# CCM4201S_MAIN_Board_V1-PIJIAKUN_20260819.net
KiCad netlist of a schematic drawn in Altium Designer
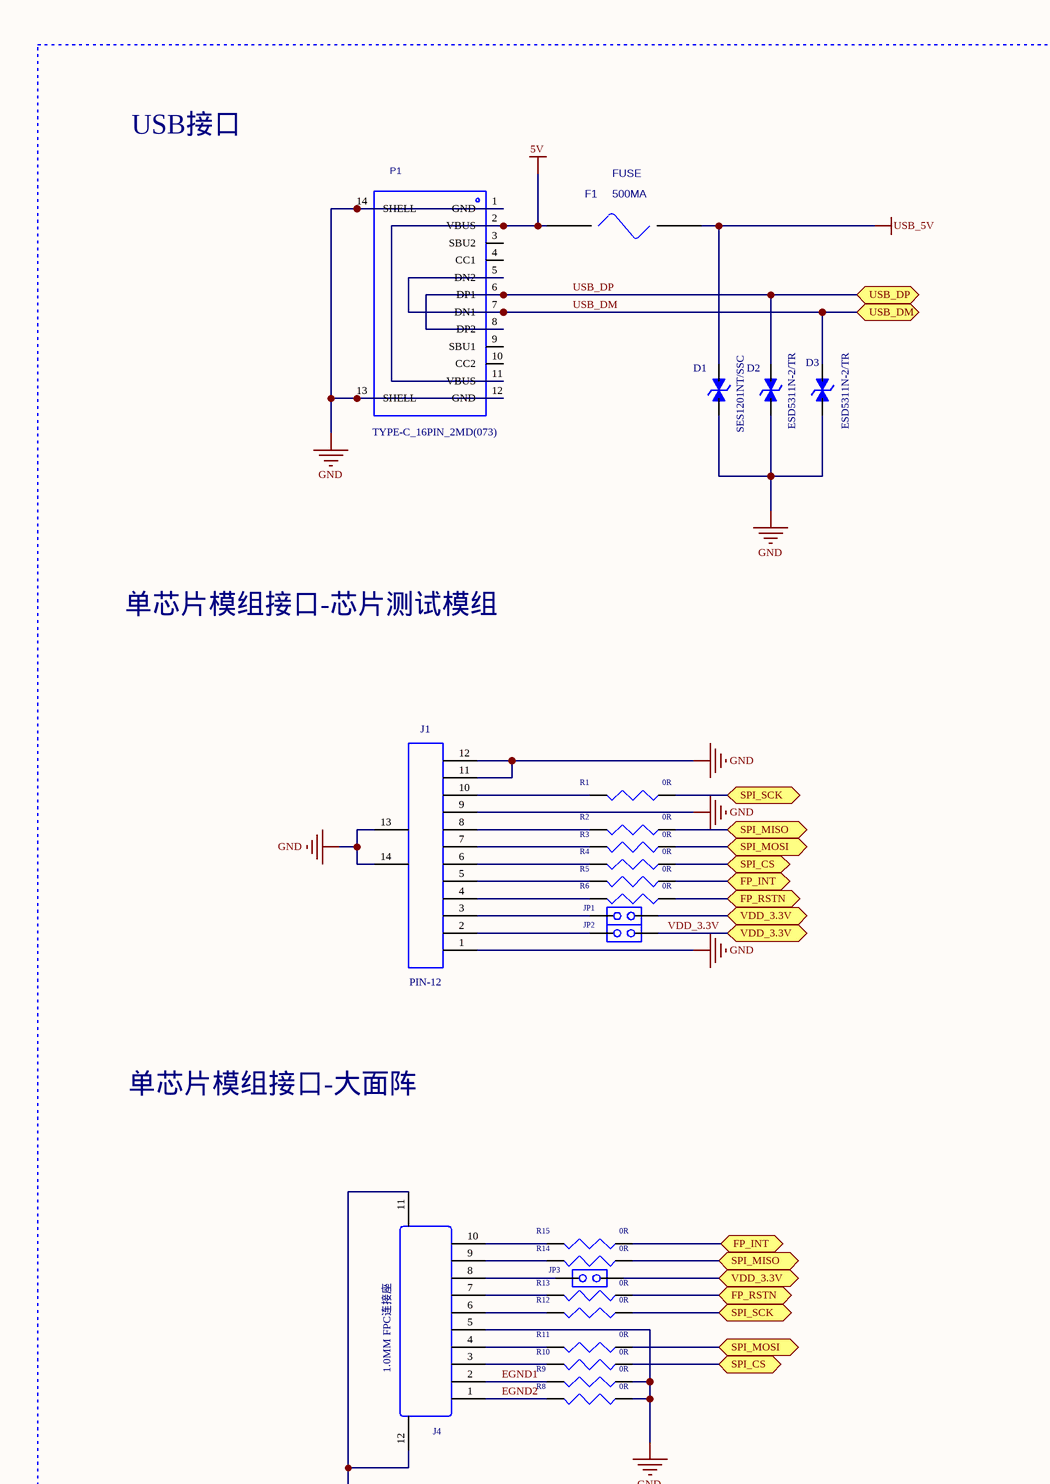
[diagram p0: CCM4201S_MAIN_Board_V1-PIJIAKUN_20260819_SCH.SchDoc, top left]
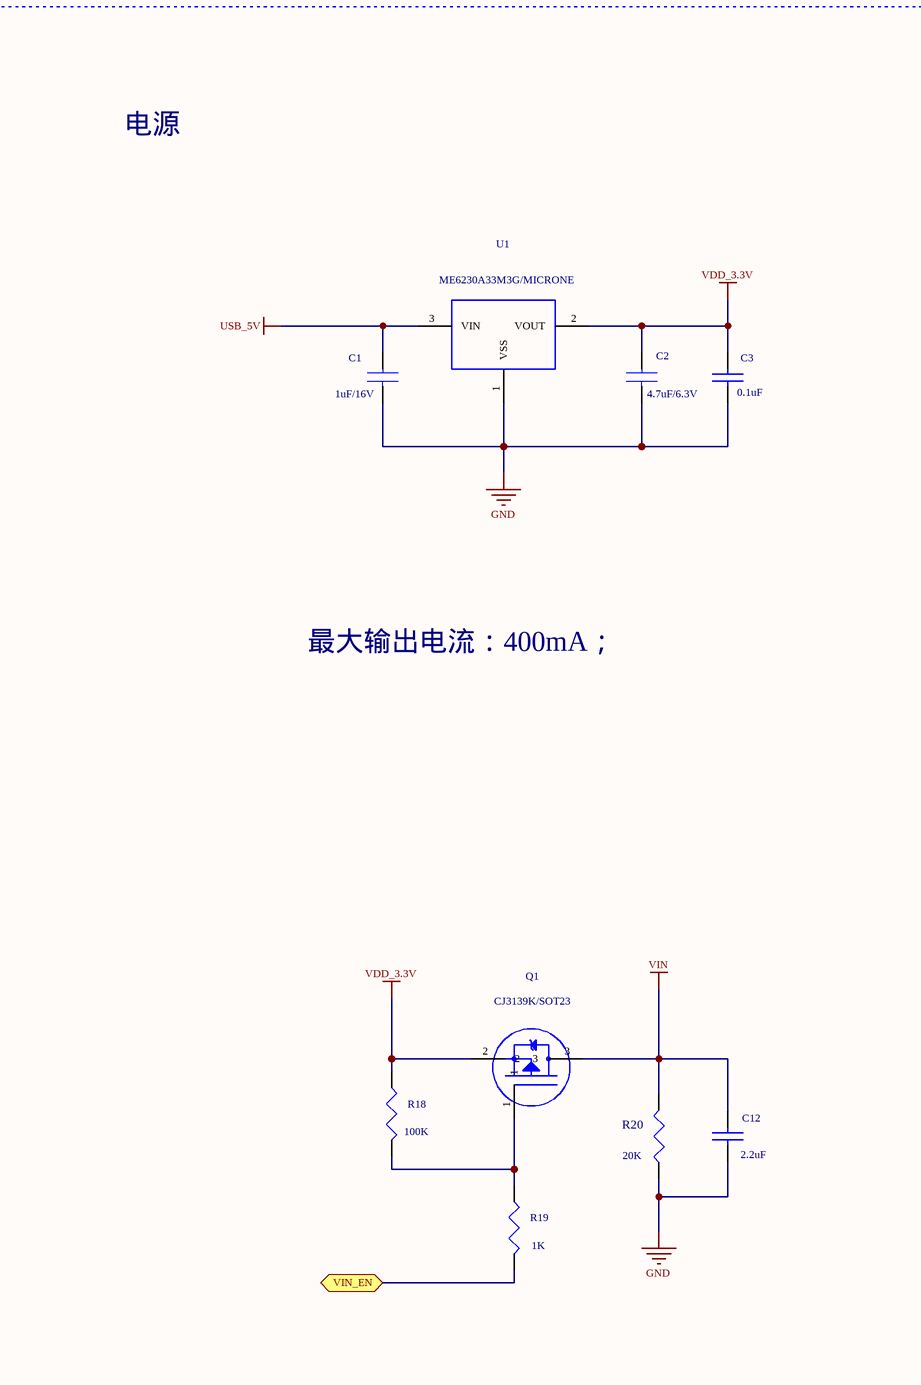
[diagram p1: CCM4201S_MAIN_Board_V1-PIJIAKUN_20260819_SCH.SchDoc, top middle]
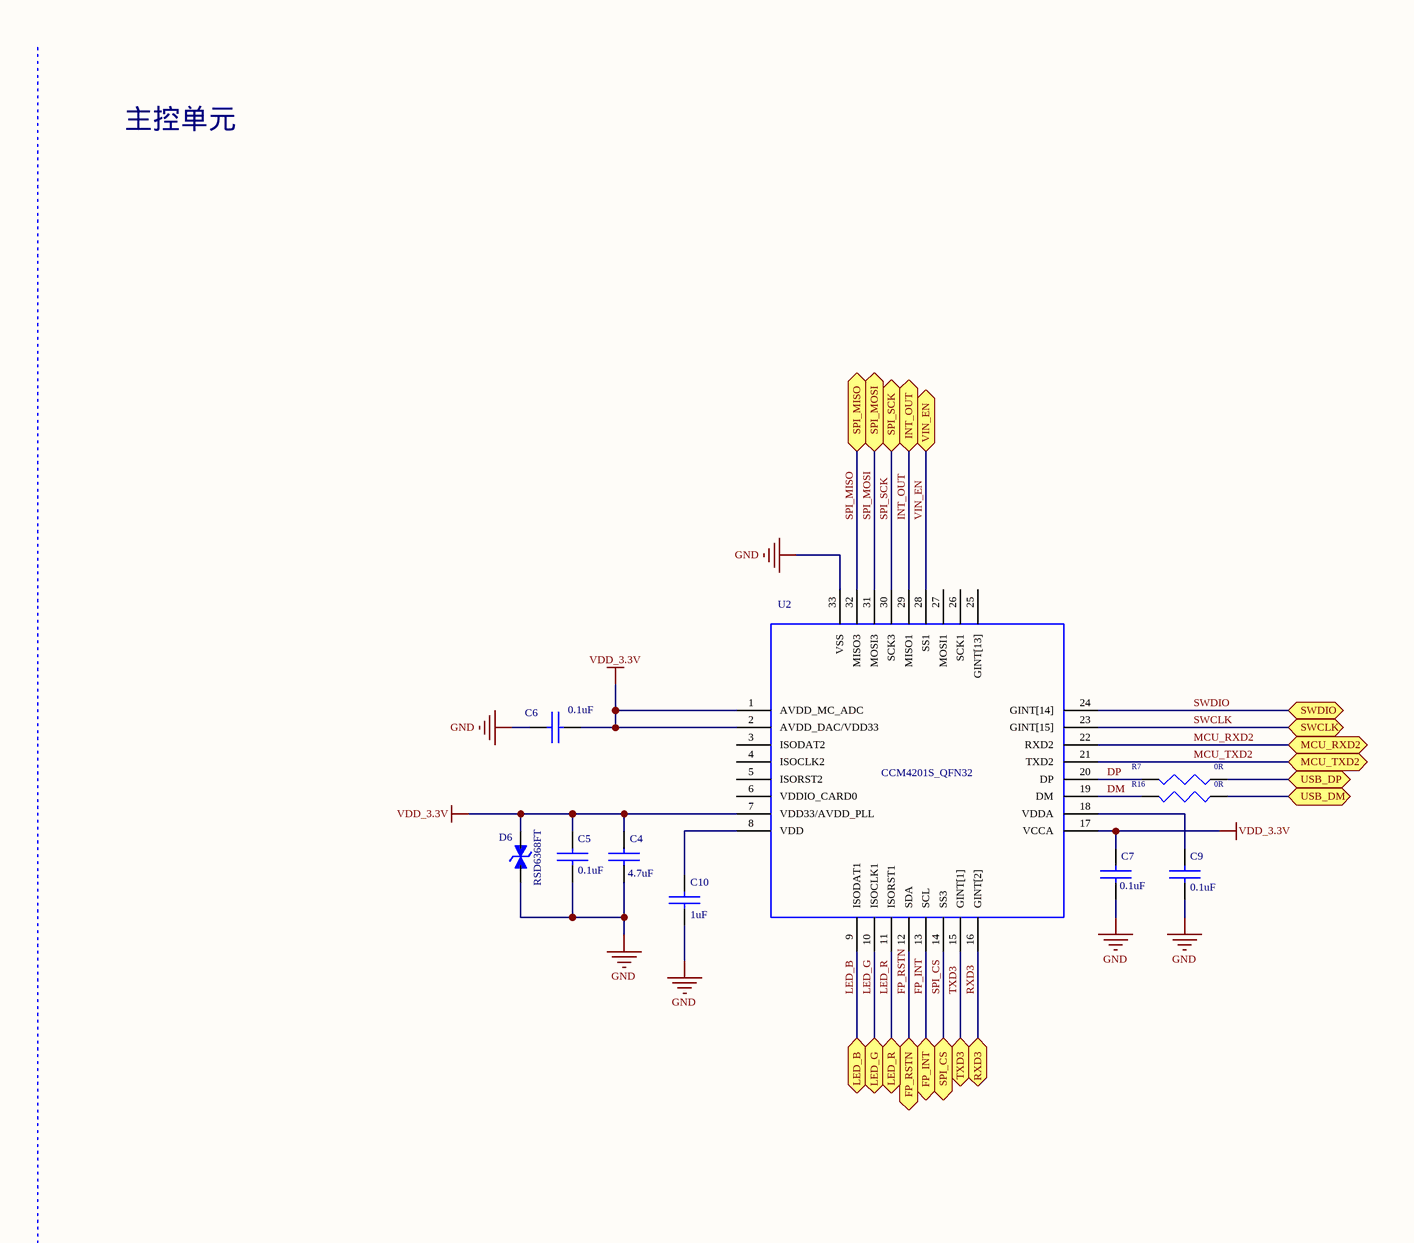
[diagram p2: CCM4201S_MAIN_Board_V1-PIJIAKUN_20260819_SCH.SchDoc, top right]
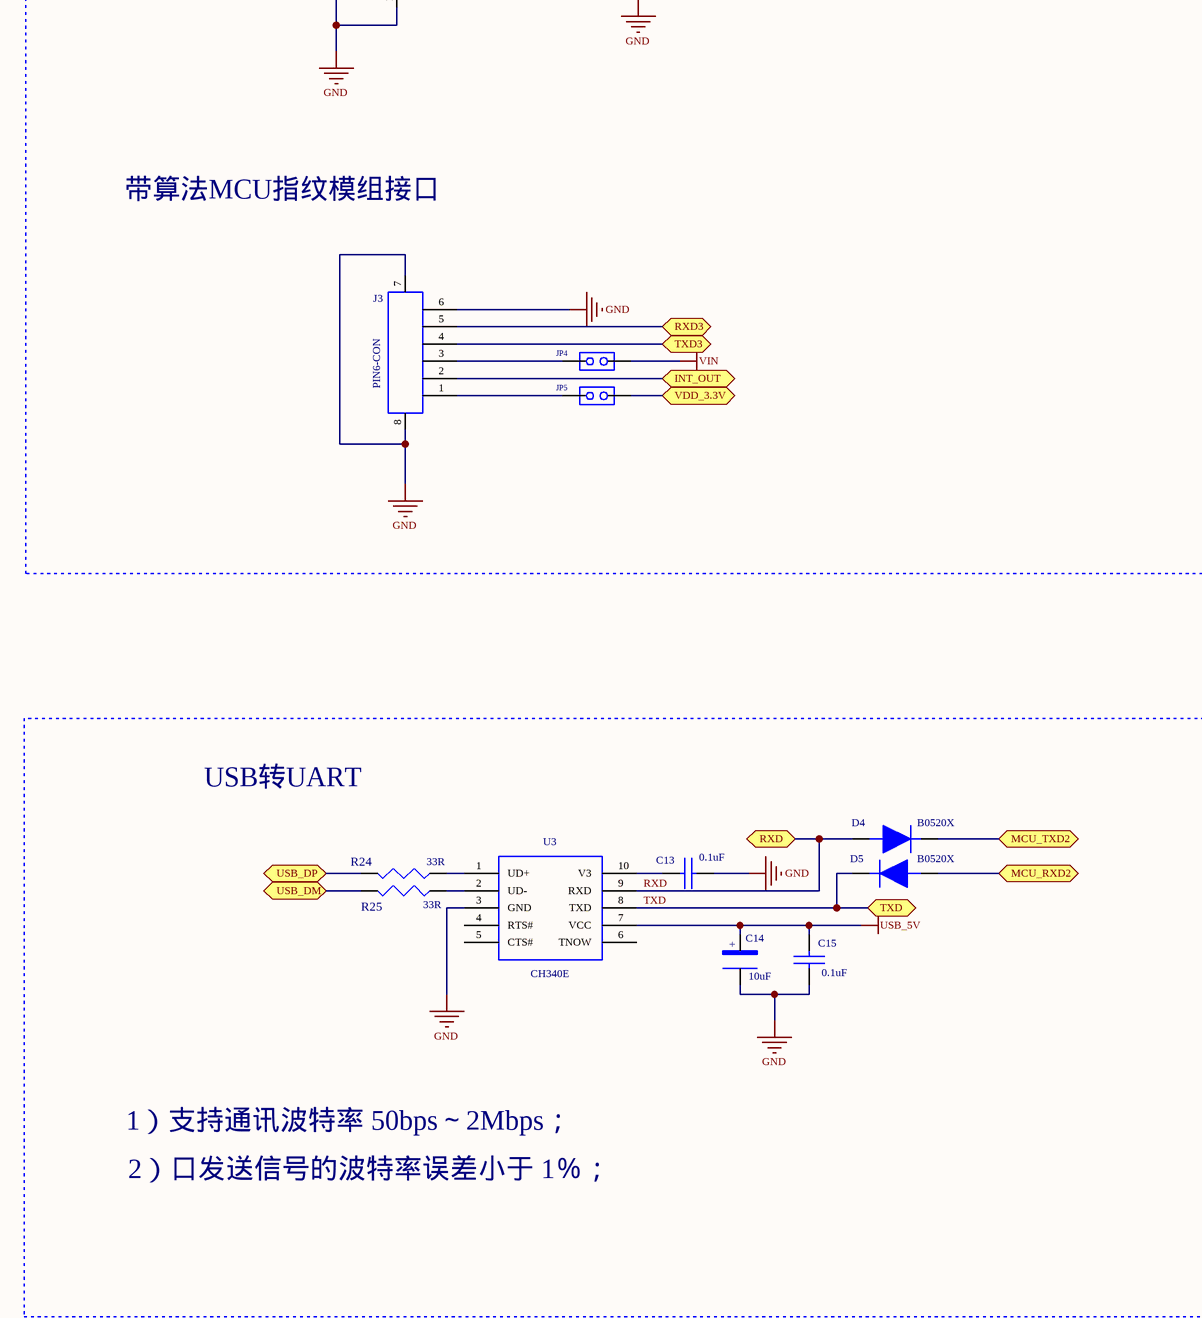
[diagram p3: CCM4201S_MAIN_Board_V1-PIJIAKUN_20260819_SCH.SchDoc, bottom left]
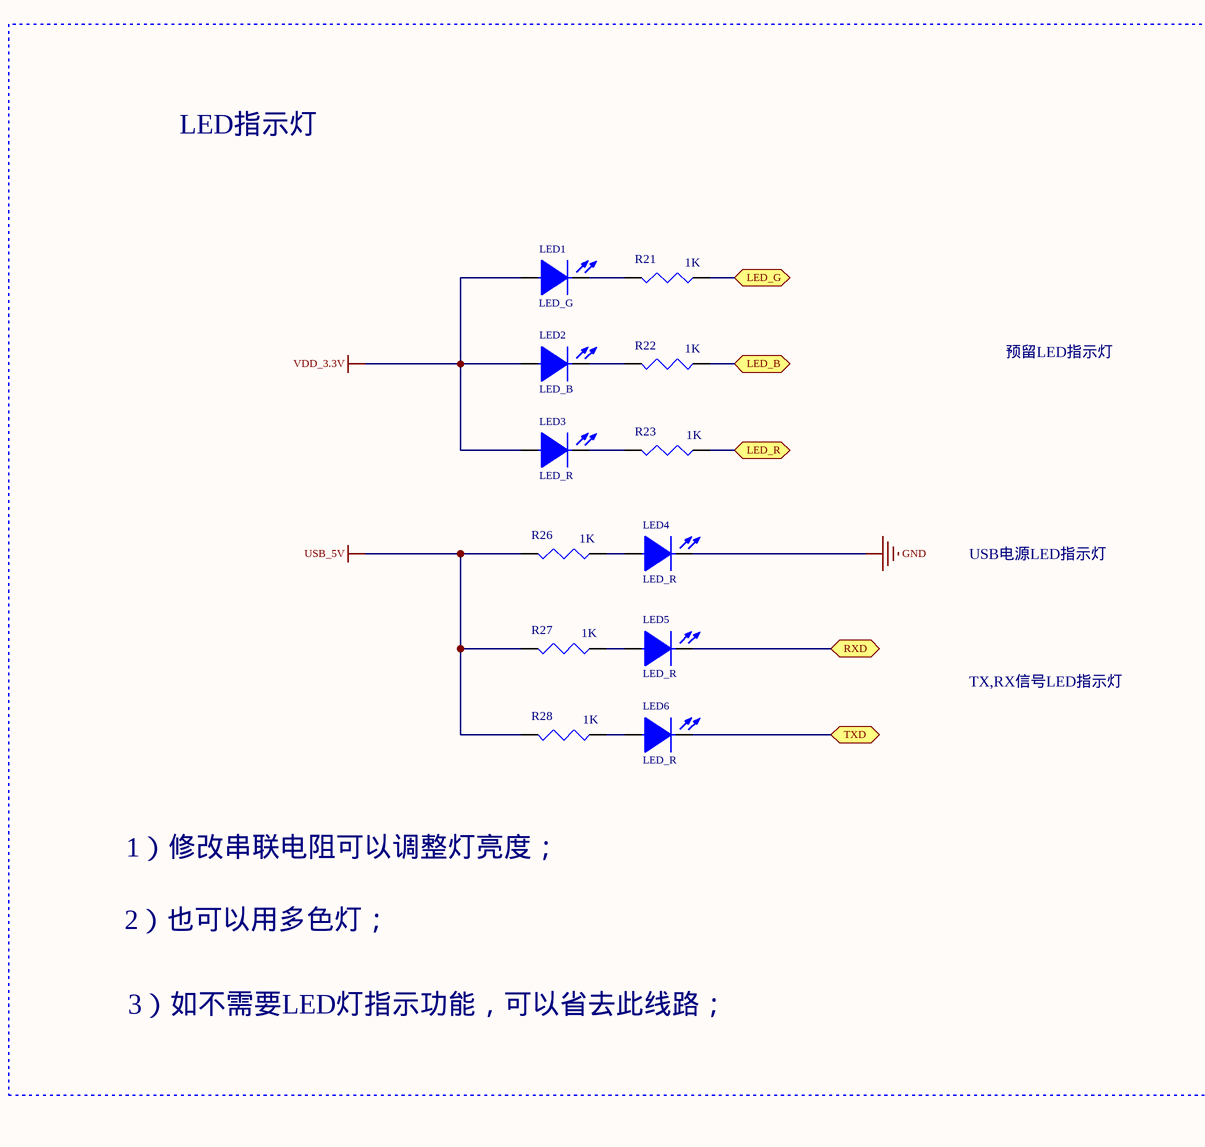
[diagram p4: CCM4201S_MAIN_Board_V1-PIJIAKUN_20260819_SCH.SchDoc, bottom middle]
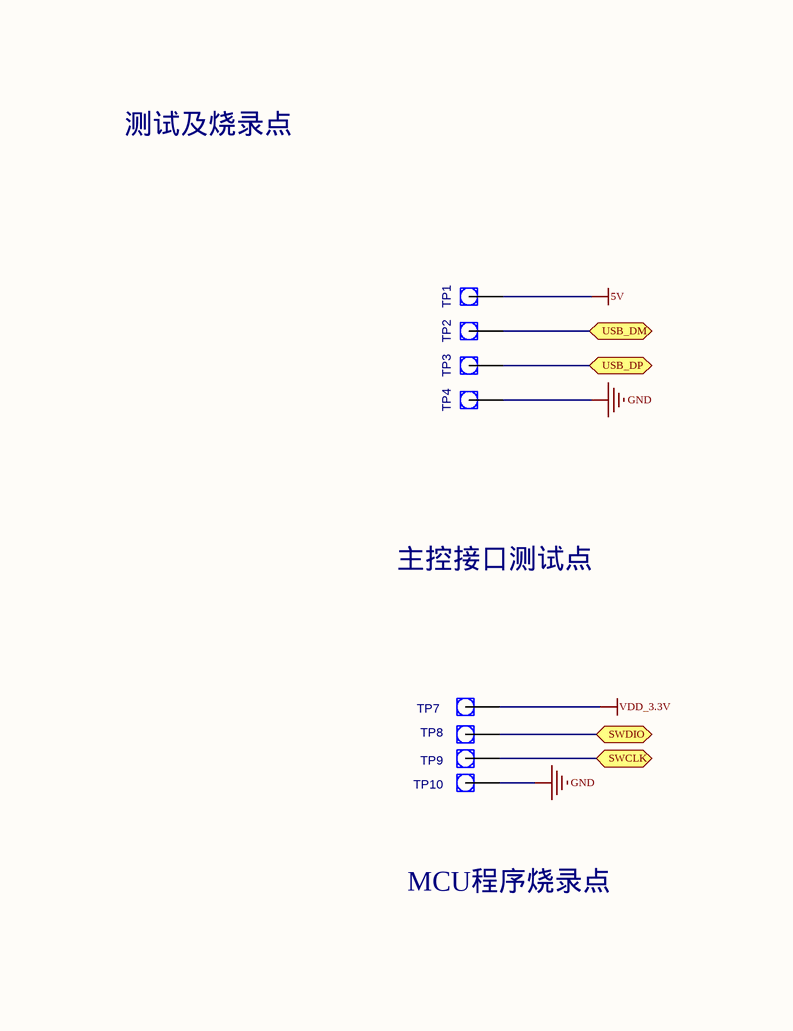
[diagram p5: CCM4201S_MAIN_Board_V1-PIJIAKUN_20260819_SCH.SchDoc, bottom right]

(export (version "E")
  (design (tool "Eeschema 10.0.6"))
  (components
    (comp (ref "C1")
      (value "1uF/16V")
      (footprint "0402C")
      (description "CAP, 10UF, 20%, 10V, X5R, 0603")
      (fields (field (name "MANUFACTURER") "muRata (村田)"))
      (libsource (lib "*") (part "C0603X"))
    )
    (comp (ref "C2")
      (value "4.7uF/6.3V")
      (footprint "0402C")
      (description "CAP, 10UF, 20%, 10V, X5R, 0603")
      (fields (field (name "MANUFACTURER") "muRata (村田)"))
      (libsource (lib "*") (part "C0603X"))
    )
    (comp (ref "C3")
      (value "0.1uF")
      (footprint "0402C")
      (description "CAP, 0.1uF, 10%, 10V, X5R, 0402")
      (libsource (lib "*") (part "C0402"))
    )
    (comp (ref "C4")
      (value "4.7uF")
      (footprint "0402C")
      (description "CAP, 1UF, 10%, 10V, X5R, 0402")
      (libsource (lib "*") (part "C0402"))
    )
    (comp (ref "C5")
      (value "0.1uF")
      (footprint "0402C")
      (description "CAP, 0.1uF, 10%, 10V, X5R, 0402")
      (libsource (lib "*") (part "C0402"))
    )
    (comp (ref "C6")
      (value "0.1uF")
      (footprint "0402C")
      (description "CAP, 0.1uF, 10%, 10V, X5R, 0402")
      (libsource (lib "*") (part "C0402"))
    )
    (comp (ref "C7")
      (value "0.1uF")
      (footprint "0402C")
      (description "CAP, 0.1uF, 10%, 10V, X5R, 0402")
      (libsource (lib "*") (part "C0402"))
    )
    (comp (ref "C9")
      (value "0.1uF")
      (footprint "0402C")
      (description "CAP, 0.1uF, 10%, 10V, X5R, 0402")
      (libsource (lib "*") (part "C0402"))
    )
    (comp (ref "C10")
      (value "1uF")
      (footprint "0402C")
      (description "CAP, 1UF, 10%, 10V, X5R, 0402")
      (libsource (lib "*") (part "C0402"))
    )
    (comp (ref "C12")
      (value "2.2uF")
      (footprint "0402C")
      (description "CAP, 2.2uF, 10%, 10V, X5R, 0201")
      (libsource (lib "*") (part "C0201"))
    )
    (comp (ref "C13")
      (value "0.1uF")
      (footprint "0402C")
      (description "CAP, 0.1uF, 10%, 10V, X5R, 0201")
      (fields
        (field (name "SOURCE_PATH") "D:\\王君资料\\客户资料\\奥美佳\\TDC5502\\SCHEMATIC\\改过原理图\\TDC5502 1210B56101MN32SSD32FTD020EARIGBT.DSN")
      )
      (libsource (lib "*") (part "C0201"))
    )
    (comp (ref "C14")
      (value "10uF")
      (footprint "L0805")
      (description "CAP, 10uF, 10%, 16V  6.3*5.3mm SMD")
      (libsource (lib "*") (part "CAP+"))
    )
    (comp (ref "C15")
      (value "0.1uF")
      (footprint "0402C")
      (description "CAP, 0.1uF, 10%, 10V, X5R, 0201")
      (fields
        (field (name "SOURCE_PATH") "D:\\王君资料\\客户资料\\奥美佳\\TDC5502\\SCHEMATIC\\改过原理图\\TDC5502 1210B56101MN32SSD32FTD020EARIGBT.DSN")
      )
      (libsource (lib "*") (part "C0201"))
    )
    (comp (ref "D1")
      (value "SES1201NT/SSC")
      (footprint "TVS0402(M)")
      (description "TVS/12V")
      (fields
        (field (name "PART NUMBER") "1.5KE220")
        (field (name "SOURCE_PATH") "D:\\工作资料\\指纹锁\\电子烟\\TF30X原理图\\TF30X-GSL6165S-V00.DSN")
      )
      (libsource (lib "*") (part "TVS0402(M)"))
    )
    (comp (ref "D2")
      (value "ESD5311N-2/TR")
      (footprint "TVS0402(M)")
      (description "TVS/5V")
      (fields
        (field (name "PART NUMBER") "1.5KE220")
        (field (name "SOURCE_PATH") "D:\\工作资料\\指纹锁\\电子烟\\TF30X原理图\\TF30X-GSL6165S-V00.DSN")
      )
      (libsource (lib "*") (part "TVS0402(M)"))
    )
    (comp (ref "D3")
      (value "ESD5311N-2/TR")
      (footprint "TVS0402(M)")
      (description "TVS/5V")
      (fields
        (field (name "PART NUMBER") "1.5KE220")
        (field (name "SOURCE_PATH") "D:\\工作资料\\指纹锁\\电子烟\\TF30X原理图\\TF30X-GSL6165S-V00.DSN")
      )
      (libsource (lib "*") (part "TVS0402(M)"))
    )
    (comp (ref "D4") (value "B0520X") (footprint "SOD523") (libsource (lib "*") (part "DIODE")))
    (comp (ref "D5") (value "B0520X") (footprint "SOD523") (libsource (lib "*") (part "DIODE")))
    (comp (ref "D6")
      (value "RSD6368FT")
      (footprint "TVS0402(M)")
      (description "TRANSIENT VOLTAGE SUPPRESSOR, VBR=220V")
      (fields
        (field (name "PART NUMBER") "1.5KE220")
        (field (name "SOURCE_PATH") "D:\\工作资料\\指纹锁\\电子烟\\TF30X原理图\\TF30X-GSL6165S-V00.DSN")
      )
      (libsource (lib "") (part "TVS0402(M)_1"))
    )
    (comp (ref "F1")
      (value "FUSE")
      (footprint "0603-PUSE")
      (fields (field (name "ALTIUM_VALUE") "500MA"))
      (libsource (lib "*") (part "FUSE"))
    )
    (comp (ref "J1") (value "PIN-12") (footprint "PIN-12") (libsource (lib "*") (part "PIN-12")))
    (comp (ref "J3") (value "PIN6-CON") (footprint "XH6PIN_1.0MM") (libsource (lib "*") (part "PIN6-CON")))
    (comp (ref "J4")
      (value "AFA01-S10FCA-00")
      (footprint "FPC-SMD_10P-P1.0_FGS-XJ-H2.0")
      (fields (field (name "BOM_SUPPLIER_PART") "C262756") (field (name "CONTRIBUTOR") "1.0MM FPC连接座"))
      (libsource (lib "*") (part "AFA01-S10FCA-00"))
    )
    (comp (ref "JP1")
      (value "CONDIP2_A")
      (footprint "PAIZHEN-1.27-2P")
      (description "Rechargeable Battery")
      (libsource (lib "CCM4201S_MAIN_Board_V1-240708") (part "CONDIP2_A"))
    )
    (comp (ref "JP2")
      (value "CONDIP2_A")
      (footprint "PAIZHEN-1.27-2P")
      (description "Rechargeable Battery")
      (libsource (lib "CCM4201S_MAIN_Board_V1-240708") (part "CONDIP2_A"))
    )
    (comp (ref "JP3")
      (value "CONDIP2_A")
      (footprint "PAIZHEN-1.27-2P")
      (description "Rechargeable Battery")
      (libsource (lib "CCM4201S_MAIN_Board_V1-240708") (part "CONDIP2_A"))
    )
    (comp (ref "JP4")
      (value "CONDIP2_A")
      (footprint "PAIZHEN-1.27-2P")
      (description "Rechargeable Battery")
      (libsource (lib "CCM4201S_MAIN_Board_V1-240708") (part "CONDIP2_A"))
    )
    (comp (ref "JP5")
      (value "CONDIP2_A")
      (footprint "PAIZHEN-1.27-2P")
      (description "Rechargeable Battery")
      (libsource (lib "CCM4201S_MAIN_Board_V1-240708") (part "CONDIP2_A"))
    )
    (comp (ref "LED1") (value "LED_G") (footprint "LED_G") (libsource (lib "*") (part "OLED")))
    (comp (ref "LED2") (value "LED_B") (footprint "LED_G") (libsource (lib "*") (part "OLED")))
    (comp (ref "LED3") (value "LED_R") (footprint "LED_G") (libsource (lib "*") (part "OLED")))
    (comp (ref "LED4") (value "LED_R") (footprint "LED_G") (libsource (lib "*") (part "OLED")))
    (comp (ref "LED5") (value "LED_R") (footprint "LED_G") (libsource (lib "*") (part "OLED")))
    (comp (ref "LED6") (value "LED_R") (footprint "LED_G") (libsource (lib "*") (part "OLED")))
    (comp (ref "P1")
      (value "TYPE-C_16PIN_2MD(073)")
      (footprint "USB-C-SMD_TYPE-C-6PIN-2MD-073")
      (fields (field (name "MANUFACTURER_PART") "TYPE-C 16PIN 2MD(073)"))
      (libsource (lib "*") (part "TYPE-C_16PIN_2MD(073)"))
    )
    (comp (ref "Q1")
      (value "CJ3139K/SOT23")
      (footprint "SOT23")
      (description "SOT23")
      (libsource (lib "*") (part "PMOS"))
    )
    (comp (ref "R1")
      (value "0R")
      (footprint "0402R")
      (description "RES,330R, 5%, 1/10W, 0201, SMD")
      (fields (field (name "Comment") "R0402"))
      (libsource (lib "*") (part "R0402"))
    )
    (comp (ref "R2")
      (value "0R")
      (footprint "0402R")
      (description "RES,330R, 5%, 1/10W, 0201, SMD")
      (fields (field (name "Comment") "R0402"))
      (libsource (lib "*") (part "R0402"))
    )
    (comp (ref "R3")
      (value "0R")
      (footprint "0402R")
      (description "RES,330R, 5%, 1/10W, 0201, SMD")
      (fields (field (name "Comment") "R0402"))
      (libsource (lib "*") (part "R0402"))
    )
    (comp (ref "R4")
      (value "0R")
      (footprint "0402R")
      (description "RES,330R, 5%, 1/10W, 0201, SMD")
      (fields (field (name "Comment") "R0402"))
      (libsource (lib "*") (part "R0402"))
    )
    (comp (ref "R5")
      (value "0R")
      (footprint "0402R")
      (description "RES,330R, 5%, 1/10W, 0201, SMD")
      (fields (field (name "Comment") "R0402"))
      (libsource (lib "*") (part "R0402"))
    )
    (comp (ref "R6")
      (value "0R")
      (footprint "0402R")
      (description "RES,330R, 5%, 1/10W, 0201, SMD")
      (fields (field (name "Comment") "R0402"))
      (libsource (lib "*") (part "R0402"))
    )
    (comp (ref "R7")
      (value "0R")
      (footprint "0402R")
      (description "RES,330R, 5%, 1/10W, 0201, SMD")
      (fields (field (name "Comment") "R0402"))
      (libsource (lib "*") (part "R0402"))
    )
    (comp (ref "R8")
      (value "0R")
      (footprint "0402R")
      (description "RES,330R, 5%, 1/10W, 0201, SMD")
      (fields (field (name "Comment") "R0402"))
      (libsource (lib "*") (part "R0402"))
    )
    (comp (ref "R9")
      (value "0R")
      (footprint "0402R")
      (description "RES,330R, 5%, 1/10W, 0201, SMD")
      (fields (field (name "Comment") "R0402"))
      (libsource (lib "*") (part "R0402"))
    )
    (comp (ref "R10")
      (value "0R")
      (footprint "0402R")
      (description "RES,330R, 5%, 1/10W, 0201, SMD")
      (fields (field (name "Comment") "R0402"))
      (libsource (lib "*") (part "R0402"))
    )
    (comp (ref "R11")
      (value "0R")
      (footprint "0402R")
      (description "RES,330R, 5%, 1/10W, 0201, SMD")
      (fields (field (name "Comment") "R0402"))
      (libsource (lib "*") (part "R0402"))
    )
    (comp (ref "R12")
      (value "0R")
      (footprint "0402R")
      (description "RES,330R, 5%, 1/10W, 0201, SMD")
      (fields (field (name "Comment") "R0402"))
      (libsource (lib "*") (part "R0402"))
    )
    (comp (ref "R13")
      (value "0R")
      (footprint "0402R")
      (description "RES,330R, 5%, 1/10W, 0201, SMD")
      (fields (field (name "Comment") "R0402"))
      (libsource (lib "*") (part "R0402"))
    )
    (comp (ref "R14")
      (value "0R")
      (footprint "0402R")
      (description "RES,330R, 5%, 1/10W, 0201, SMD")
      (fields (field (name "Comment") "R0402"))
      (libsource (lib "*") (part "R0402"))
    )
    (comp (ref "R15")
      (value "0R")
      (footprint "0402R")
      (description "RES,330R, 5%, 1/10W, 0201, SMD")
      (fields (field (name "Comment") "R0402"))
      (libsource (lib "*") (part "R0402"))
    )
    (comp (ref "R16")
      (value "0R")
      (footprint "0402R")
      (description "RES,330R, 5%, 1/10W, 0201, SMD")
      (fields (field (name "Comment") "R0402"))
      (libsource (lib "*") (part "R0402"))
    )
    (comp (ref "R18")
      (value "100K")
      (footprint "0402R")
      (description "RES 0603  4.7KΩ±1%  1/8W")
      (libsource (lib "*") (part "R0402H"))
    )
    (comp (ref "R19")
      (value "1K")
      (footprint "0402R")
      (description "RES 0603  4.7KΩ±1%  1/8W")
      (libsource (lib "*") (part "R0402H"))
    )
    (comp (ref "R20")
      (value "20K")
      (footprint "0402R")
      (description "RES,20K, 5%, 1/10W, 0201, SMD")
      (libsource (lib "*") (part "R0402"))
    )
    (comp (ref "R21")
      (value "1K")
      (footprint "0402R")
      (description "RES,20K, 5%, 1/10W, 0201, SMD")
      (libsource (lib "*") (part "R0402"))
    )
    (comp (ref "R22")
      (value "1K")
      (footprint "0402R")
      (description "RES,20K, 5%, 1/10W, 0201, SMD")
      (libsource (lib "*") (part "R0402"))
    )
    (comp (ref "R23")
      (value "1K")
      (footprint "0402R")
      (description "RES,20K, 5%, 1/10W, 0201, SMD")
      (libsource (lib "*") (part "R0402"))
    )
    (comp (ref "R24") (value "33R") (footprint "0402R") (libsource (lib "*") (part "R0201")))
    (comp (ref "R25") (value "33R") (footprint "0402R") (libsource (lib "*") (part "R0201")))
    (comp (ref "R26")
      (value "1K")
      (footprint "0402R")
      (description "RES,20K, 5%, 1/10W, 0201, SMD")
      (libsource (lib "*") (part "R0402"))
    )
    (comp (ref "R27")
      (value "1K")
      (footprint "0402R")
      (description "RES,20K, 5%, 1/10W, 0201, SMD")
      (libsource (lib "*") (part "R0402"))
    )
    (comp (ref "R28")
      (value "1K")
      (footprint "0402R")
      (description "RES,20K, 5%, 1/10W, 0201, SMD")
      (libsource (lib "*") (part "R0402"))
    )
    (comp (ref "TP1")
      (value "TP12")
      (footprint "TPAA")
      (description "测试点，不需要贴片")
      (libsource (lib "*") (part "TP12"))
    )
    (comp (ref "TP2")
      (value "TP12")
      (footprint "TPAA")
      (description "测试点，不需要贴片")
      (libsource (lib "*") (part "TP12"))
    )
    (comp (ref "TP3")
      (value "TP12")
      (footprint "TPAA")
      (description "测试点，不需要贴片")
      (libsource (lib "*") (part "TP12"))
    )
    (comp (ref "TP4")
      (value "TP12")
      (footprint "TPAA")
      (description "测试点，不需要贴片")
      (libsource (lib "*") (part "TP12"))
    )
    (comp (ref "TP7")
      (value "TP12")
      (footprint "TPAA")
      (description "测试点，不需要贴片")
      (libsource (lib "*") (part "TP12"))
    )
    (comp (ref "TP8")
      (value "TP12")
      (footprint "TPAA")
      (description "测试点，不需要贴片")
      (libsource (lib "*") (part "TP12"))
    )
    (comp (ref "TP9")
      (value "TP12")
      (footprint "TPAA")
      (description "测试点，不需要贴片")
      (libsource (lib "*") (part "TP12"))
    )
    (comp (ref "TP10")
      (value "TP12")
      (footprint "TPAA")
      (description "测试点，不需要贴片")
      (libsource (lib "*") (part "TP12"))
    )
    (comp (ref "U1")
      (value "ME6230A33M3G/MICRONE")
      (footprint "SOT23-3")
      (description "3.3V  SOT23-3")
      (libsource (lib "*") (part "TCS2115_C33"))
    )
    (comp (ref "U2")
      (value "CCM4201S_QFN32")
      (footprint "QFN32_4X4_0.4")
      (libsource (lib "*") (part "CCM4201S_QFN32"))
    )
    (comp (ref "U3") (value "CH340E") (footprint "MSOP-10") (libsource (lib "*") (part "CH340E")))
  )
  (nets
    (net (code "1") (name "/DM") (class "Default")
      (node (ref "R16") (pin "2") (pinfunction "2_2") (pintype "passive"))
      (node (ref "U2") (pin "19") (pinfunction "DM_19") (pintype "passive"))
    )
    (net (code "2") (name "/DP") (class "Default")
      (node (ref "R7") (pin "2") (pinfunction "2_2") (pintype "passive"))
      (node (ref "U2") (pin "20") (pinfunction "DP_20") (pintype "passive"))
    )
    (net (code "3") (name "/EGND1") (class "Default")
      (node (ref "J4") (pin "2") (pinfunction "2_2") (pintype "passive"))
      (node (ref "R9") (pin "2") (pinfunction "2_2") (pintype "passive"))
    )
    (net (code "4") (name "/EGND2") (class "Default")
      (node (ref "J4") (pin "1") (pinfunction "1_1") (pintype "passive"))
      (node (ref "R8") (pin "2") (pinfunction "2_2") (pintype "passive"))
    )
    (net (code "5") (name "/FP_INT") (class "Default")
      (node (ref "R15") (pin "1") (pinfunction "1_1") (pintype "passive"))
      (node (ref "R5") (pin "1") (pinfunction "1_1") (pintype "passive"))
      (node (ref "U2") (pin "13") (pinfunction "SCL_13") (pintype "passive"))
    )
    (net (code "6") (name "/FP_RSTN") (class "Default")
      (node (ref "R13") (pin "1") (pinfunction "1_1") (pintype "passive"))
      (node (ref "R6") (pin "1") (pinfunction "1_1") (pintype "passive"))
      (node (ref "U2") (pin "12") (pinfunction "SDA_12") (pintype "passive"))
    )
    (net (code "7") (name "/INT_OUT") (class "Default")
      (node (ref "J3") (pin "2") (pinfunction "2_2") (pintype "passive"))
      (node (ref "U2") (pin "29") (pinfunction "MISO1_29") (pintype "passive"))
    )
    (net (code "8") (name "/LED_B") (class "Default")
      (node (ref "R22") (pin "1") (pinfunction "1_1") (pintype "passive"))
      (node (ref "U2") (pin "9") (pinfunction "ISODAT1_9") (pintype "passive"))
    )
    (net (code "9") (name "/LED_G") (class "Default")
      (node (ref "R21") (pin "1") (pinfunction "1_1") (pintype "passive"))
      (node (ref "U2") (pin "10") (pinfunction "ISOCLK1_10") (pintype "passive"))
    )
    (net (code "10") (name "/LED_R") (class "Default")
      (node (ref "R23") (pin "1") (pinfunction "1_1") (pintype "passive"))
      (node (ref "U2") (pin "11") (pinfunction "ISORST1_11") (pintype "passive"))
    )
    (net (code "11") (name "/MCU_RXD2") (class "Default")
      (node (ref "D5") (pin "A") (pinfunction "A_A") (pintype "passive"))
      (node (ref "U2") (pin "22") (pinfunction "RXD2_22") (pintype "passive"))
    )
    (net (code "12") (name "/MCU_TXD2") (class "Default")
      (node (ref "D4") (pin "K") (pinfunction "K_K") (pintype "passive"))
      (node (ref "U2") (pin "21") (pinfunction "TXD2_21") (pintype "passive"))
    )
    (net (code "13") (name "/RXD") (class "Default")
      (node (ref "D4") (pin "A") (pinfunction "A_A") (pintype "passive"))
      (node (ref "LED5") (pin "2") (pinfunction "2_2") (pintype "passive"))
      (node (ref "U3") (pin "9") (pinfunction "RXD_9") (pintype "passive"))
    )
    (net (code "14") (name "/RXD3") (class "Default")
      (node (ref "J3") (pin "5") (pinfunction "5_5") (pintype "passive"))
      (node (ref "U2") (pin "16") (pinfunction "GINT[2]_16") (pintype "passive"))
    )
    (net (code "15") (name "/SPI_CS") (class "Default")
      (node (ref "R10") (pin "1") (pinfunction "1_1") (pintype "passive"))
      (node (ref "R4") (pin "1") (pinfunction "1_1") (pintype "passive"))
      (node (ref "U2") (pin "14") (pinfunction "SS3_14") (pintype "passive"))
    )
    (net (code "16") (name "/SPI_MISO") (class "Default")
      (node (ref "R14") (pin "1") (pinfunction "1_1") (pintype "passive"))
      (node (ref "R2") (pin "1") (pinfunction "1_1") (pintype "passive"))
      (node (ref "U2") (pin "32") (pinfunction "MISO3_32") (pintype "passive"))
    )
    (net (code "17") (name "/SPI_MOSI") (class "Default")
      (node (ref "R11") (pin "1") (pinfunction "1_1") (pintype "passive"))
      (node (ref "R3") (pin "1") (pinfunction "1_1") (pintype "passive"))
      (node (ref "U2") (pin "31") (pinfunction "MOSI3_31") (pintype "passive"))
    )
    (net (code "18") (name "/SPI_SCK") (class "Default")
      (node (ref "R1") (pin "1") (pinfunction "1_1") (pintype "passive"))
      (node (ref "R12") (pin "1") (pinfunction "1_1") (pintype "passive"))
      (node (ref "U2") (pin "30") (pinfunction "SCK3_30") (pintype "passive"))
    )
    (net (code "19") (name "/SWCLK") (class "Default")
      (node (ref "TP9") (pin "1") (pinfunction "1_1") (pintype "passive"))
      (node (ref "U2") (pin "23") (pinfunction "GINT[15]_23") (pintype "passive"))
    )
    (net (code "20") (name "/SWDIO") (class "Default")
      (node (ref "TP8") (pin "1") (pinfunction "1_1") (pintype "passive"))
      (node (ref "U2") (pin "24") (pinfunction "GINT[14]_24") (pintype "passive"))
    )
    (net (code "21") (name "/TXD") (class "Default")
      (node (ref "D5") (pin "K") (pinfunction "K_K") (pintype "passive"))
      (node (ref "LED6") (pin "2") (pinfunction "2_2") (pintype "passive"))
      (node (ref "U3") (pin "8") (pinfunction "TXD_8") (pintype "passive"))
    )
    (net (code "22") (name "/TXD3") (class "Default")
      (node (ref "J3") (pin "4") (pinfunction "4_4") (pintype "passive"))
      (node (ref "U2") (pin "15") (pinfunction "GINT[1]_15") (pintype "passive"))
    )
    (net (code "23") (name "/USB_DM") (class "Default")
      (node (ref "D3") (pin "2") (pinfunction "2_2") (pintype "passive"))
      (node (ref "P1") (pin "5") (pinfunction "DN2_5") (pintype "passive"))
      (node (ref "P1") (pin "7") (pinfunction "DN1_7") (pintype "passive"))
      (node (ref "R16") (pin "1") (pinfunction "1_1") (pintype "passive"))
      (node (ref "R25") (pin "2") (pinfunction "2_2") (pintype "passive"))
      (node (ref "TP2") (pin "1") (pinfunction "1_1") (pintype "passive"))
    )
    (net (code "24") (name "/USB_DP") (class "Default")
      (node (ref "D2") (pin "2") (pinfunction "2_2") (pintype "passive"))
      (node (ref "P1") (pin "6") (pinfunction "DP1_6") (pintype "passive"))
      (node (ref "P1") (pin "8") (pinfunction "DP2_8") (pintype "passive"))
      (node (ref "R24") (pin "2") (pinfunction "2_2") (pintype "passive"))
      (node (ref "R7") (pin "1") (pinfunction "1_1") (pintype "passive"))
      (node (ref "TP3") (pin "1") (pinfunction "1_1") (pintype "passive"))
    )
    (net (code "25") (name "/VIN_EN") (class "Default")
      (node (ref "R19") (pin "1") (pinfunction "1_1") (pintype "passive"))
      (node (ref "U2") (pin "28") (pinfunction "SS1_28") (pintype "passive"))
    )
    (net (code "26") (name "5V") (class "Default")
      (node (ref "F1") (pin "1") (pinfunction "1_1") (pintype "passive"))
      (node (ref "P1") (pin "11") (pinfunction "VBUS_11") (pintype "passive"))
      (node (ref "P1") (pin "2") (pinfunction "VBUS_2") (pintype "passive"))
      (node (ref "TP1") (pin "1") (pinfunction "1_1") (pintype "passive"))
    )
    (net (code "27") (name "GND") (class "Default")
      (node (ref "C1") (pin "2") (pinfunction "2_2") (pintype "passive"))
      (node (ref "C10") (pin "2") (pinfunction "2_2") (pintype "passive"))
      (node (ref "C12") (pin "2") (pinfunction "2_2") (pintype "passive"))
      (node (ref "C13") (pin "2") (pinfunction "2_2") (pintype "passive"))
      (node (ref "C14") (pin "2") (pinfunction "2_2") (pintype "passive"))
      (node (ref "C15") (pin "2") (pinfunction "2_2") (pintype "passive"))
      (node (ref "C2") (pin "2") (pinfunction "2_2") (pintype "passive"))
      (node (ref "C3") (pin "2") (pinfunction "2_2") (pintype "passive"))
      (node (ref "C4") (pin "2") (pinfunction "2_2") (pintype "passive"))
      (node (ref "C5") (pin "2") (pinfunction "2_2") (pintype "passive"))
      (node (ref "C6") (pin "1") (pinfunction "1_1") (pintype "passive"))
      (node (ref "C7") (pin "2") (pinfunction "2_2") (pintype "passive"))
      (node (ref "C9") (pin "2") (pinfunction "2_2") (pintype "passive"))
      (node (ref "D1") (pin "1") (pinfunction "1_1") (pintype "passive"))
      (node (ref "D2") (pin "1") (pinfunction "1_1") (pintype "passive"))
      (node (ref "D3") (pin "1") (pinfunction "1_1") (pintype "passive"))
      (node (ref "D6") (pin "2") (pinfunction "2_2") (pintype "passive"))
      (node (ref "J1") (pin "1") (pinfunction "1_1") (pintype "passive"))
      (node (ref "J1") (pin "11") (pinfunction "11_11") (pintype "passive"))
      (node (ref "J1") (pin "12") (pinfunction "12_12") (pintype "passive"))
      (node (ref "J1") (pin "13") (pinfunction "13_13") (pintype "passive"))
      (node (ref "J1") (pin "14") (pinfunction "14_14") (pintype "passive"))
      (node (ref "J1") (pin "9") (pinfunction "9_9") (pintype "passive"))
      (node (ref "J3") (pin "6") (pinfunction "6_6") (pintype "passive"))
      (node (ref "J3") (pin "7") (pinfunction "7_7") (pintype "passive"))
      (node (ref "J3") (pin "8") (pinfunction "8_8") (pintype "passive"))
      (node (ref "J4") (pin "11") (pinfunction "11_11") (pintype "passive"))
      (node (ref "J4") (pin "12") (pinfunction "12_12") (pintype "passive"))
      (node (ref "J4") (pin "5") (pinfunction "5_5") (pintype "passive"))
      (node (ref "LED4") (pin "2") (pinfunction "2_2") (pintype "passive"))
      (node (ref "P1") (pin "1") (pinfunction "GND_1") (pintype "passive"))
      (node (ref "P1") (pin "12") (pinfunction "GND_12") (pintype "passive"))
      (node (ref "P1") (pin "13") (pinfunction "SHELL_13") (pintype "passive"))
      (node (ref "P1") (pin "14") (pinfunction "SHELL_14") (pintype "passive"))
      (node (ref "R20") (pin "1") (pinfunction "1_1") (pintype "passive"))
      (node (ref "R8") (pin "1") (pinfunction "1_1") (pintype "passive"))
      (node (ref "R9") (pin "1") (pinfunction "1_1") (pintype "passive"))
      (node (ref "TP10") (pin "1") (pinfunction "1_1") (pintype "passive"))
      (node (ref "TP4") (pin "1") (pinfunction "1_1") (pintype "passive"))
      (node (ref "U1") (pin "1") (pinfunction "VSS_1") (pintype "passive"))
      (node (ref "U2") (pin "33") (pinfunction "VSS_33") (pintype "passive"))
      (node (ref "U3") (pin "3") (pinfunction "GND_3") (pintype "passive"))
    )
    (net (code "28") (name "Net-(J1-Pad2)") (class "Default")
      (node (ref "J1") (pin "2") (pinfunction "2_2") (pintype "passive"))
      (node (ref "JP2") (pin "2") (pinfunction "2_2") (pintype "passive"))
    )
    (net (code "29") (name "Net-(J1-Pad3)") (class "Default")
      (node (ref "J1") (pin "3") (pinfunction "3_3") (pintype "passive"))
      (node (ref "JP1") (pin "2") (pinfunction "2_2") (pintype "passive"))
    )
    (net (code "30") (name "Net-(J1-Pad4)") (class "Default")
      (node (ref "J1") (pin "4") (pinfunction "4_4") (pintype "passive"))
      (node (ref "R6") (pin "2") (pinfunction "2_2") (pintype "passive"))
    )
    (net (code "31") (name "Net-(J1-Pad5)") (class "Default")
      (node (ref "J1") (pin "5") (pinfunction "5_5") (pintype "passive"))
      (node (ref "R5") (pin "2") (pinfunction "2_2") (pintype "passive"))
    )
    (net (code "32") (name "Net-(J1-Pad6)") (class "Default")
      (node (ref "J1") (pin "6") (pinfunction "6_6") (pintype "passive"))
      (node (ref "R4") (pin "2") (pinfunction "2_2") (pintype "passive"))
    )
    (net (code "33") (name "Net-(J1-Pad7)") (class "Default")
      (node (ref "J1") (pin "7") (pinfunction "7_7") (pintype "passive"))
      (node (ref "R3") (pin "2") (pinfunction "2_2") (pintype "passive"))
    )
    (net (code "34") (name "Net-(J1-Pad8)") (class "Default")
      (node (ref "J1") (pin "8") (pinfunction "8_8") (pintype "passive"))
      (node (ref "R2") (pin "2") (pinfunction "2_2") (pintype "passive"))
    )
    (net (code "35") (name "Net-(J1-Pad10)") (class "Default")
      (node (ref "J1") (pin "10") (pinfunction "10_10") (pintype "passive"))
      (node (ref "R1") (pin "2") (pinfunction "2_2") (pintype "passive"))
    )
    (net (code "36") (name "Net-(J3-Pad1)") (class "Default")
      (node (ref "J3") (pin "1") (pinfunction "1_1") (pintype "passive"))
      (node (ref "JP5") (pin "2") (pinfunction "2_2") (pintype "passive"))
    )
    (net (code "37") (name "Net-(J3-Pad3)") (class "Default")
      (node (ref "J3") (pin "3") (pinfunction "3_3") (pintype "passive"))
      (node (ref "JP4") (pin "2") (pinfunction "2_2") (pintype "passive"))
    )
    (net (code "38") (name "Net-(J4-Pad3)") (class "Default")
      (node (ref "J4") (pin "3") (pinfunction "3_3") (pintype "passive"))
      (node (ref "R10") (pin "2") (pinfunction "2_2") (pintype "passive"))
    )
    (net (code "39") (name "Net-(J4-Pad4)") (class "Default")
      (node (ref "J4") (pin "4") (pinfunction "4_4") (pintype "passive"))
      (node (ref "R11") (pin "2") (pinfunction "2_2") (pintype "passive"))
    )
    (net (code "40") (name "Net-(J4-Pad6)") (class "Default")
      (node (ref "J4") (pin "6") (pinfunction "6_6") (pintype "passive"))
      (node (ref "R12") (pin "2") (pinfunction "2_2") (pintype "passive"))
    )
    (net (code "41") (name "Net-(J4-Pad7)") (class "Default")
      (node (ref "J4") (pin "7") (pinfunction "7_7") (pintype "passive"))
      (node (ref "R13") (pin "2") (pinfunction "2_2") (pintype "passive"))
    )
    (net (code "42") (name "Net-(J4-Pad8)") (class "Default")
      (node (ref "J4") (pin "8") (pinfunction "8_8") (pintype "passive"))
      (node (ref "JP3") (pin "2") (pinfunction "2_2") (pintype "passive"))
    )
    (net (code "43") (name "Net-(J4-Pad9)") (class "Default")
      (node (ref "J4") (pin "9") (pinfunction "9_9") (pintype "passive"))
      (node (ref "R14") (pin "2") (pinfunction "2_2") (pintype "passive"))
    )
    (net (code "44") (name "Net-(J4-Pad10)") (class "Default")
      (node (ref "J4") (pin "10") (pinfunction "10_10") (pintype "passive"))
      (node (ref "R15") (pin "2") (pinfunction "2_2") (pintype "passive"))
    )
    (net (code "45") (name "Net-(LED1-Pad2)") (class "Default")
      (node (ref "LED1") (pin "2") (pinfunction "2_2") (pintype "passive"))
      (node (ref "R21") (pin "2") (pinfunction "2_2") (pintype "passive"))
    )
    (net (code "46") (name "Net-(LED2-Pad2)") (class "Default")
      (node (ref "LED2") (pin "2") (pinfunction "2_2") (pintype "passive"))
      (node (ref "R22") (pin "2") (pinfunction "2_2") (pintype "passive"))
    )
    (net (code "47") (name "Net-(LED3-Pad2)") (class "Default")
      (node (ref "LED3") (pin "2") (pinfunction "2_2") (pintype "passive"))
      (node (ref "R23") (pin "2") (pinfunction "2_2") (pintype "passive"))
    )
    (net (code "48") (name "Net-(LED4-Pad1)") (class "Default")
      (node (ref "LED4") (pin "1") (pinfunction "1_1") (pintype "passive"))
      (node (ref "R26") (pin "1") (pinfunction "1_1") (pintype "passive"))
    )
    (net (code "49") (name "Net-(LED5-Pad1)") (class "Default")
      (node (ref "LED5") (pin "1") (pinfunction "1_1") (pintype "passive"))
      (node (ref "R27") (pin "1") (pinfunction "1_1") (pintype "passive"))
    )
    (net (code "50") (name "Net-(LED6-Pad1)") (class "Default")
      (node (ref "LED6") (pin "1") (pinfunction "1_1") (pintype "passive"))
      (node (ref "R28") (pin "1") (pinfunction "1_1") (pintype "passive"))
    )
    (net (code "51") (name "Net-(Q1-Pad1)") (class "Default")
      (node (ref "Q1") (pin "1") (pinfunction "1_1") (pintype "passive"))
      (node (ref "R18") (pin "1") (pinfunction "1_1") (pintype "passive"))
      (node (ref "R19") (pin "2") (pinfunction "2_2") (pintype "passive"))
    )
    (net (code "52") (name "Net-(U2-VDD)") (class "Default")
      (node (ref "C10") (pin "1") (pinfunction "1_1") (pintype "passive"))
      (node (ref "U2") (pin "8") (pinfunction "VDD_8") (pintype "passive"))
    )
    (net (code "53") (name "Net-(U2-VDDA)") (class "Default")
      (node (ref "C9") (pin "1") (pinfunction "1_1") (pintype "passive"))
      (node (ref "U2") (pin "18") (pinfunction "VDDA_18") (pintype "passive"))
    )
    (net (code "54") (name "Net-(U3-UD+)") (class "Default")
      (node (ref "R24") (pin "1") (pinfunction "1_1") (pintype "passive"))
      (node (ref "U3") (pin "1") (pinfunction "UD+_1") (pintype "passive"))
    )
    (net (code "55") (name "Net-(U3-UD-)") (class "Default")
      (node (ref "R25") (pin "1") (pinfunction "1_1") (pintype "passive"))
      (node (ref "U3") (pin "2") (pinfunction "UD-_2") (pintype "passive"))
    )
    (net (code "56") (name "Net-(U3-V3)") (class "Default")
      (node (ref "C13") (pin "1") (pinfunction "1_1") (pintype "passive"))
      (node (ref "U3") (pin "10") (pinfunction "V3_10") (pintype "passive"))
    )
    (net (code "57") (name "USB_5V") (class "Default")
      (node (ref "C1") (pin "1") (pinfunction "1_1") (pintype "passive"))
      (node (ref "C14") (pin "1") (pinfunction "1_1") (pintype "passive"))
      (node (ref "C15") (pin "1") (pinfunction "1_1") (pintype "passive"))
      (node (ref "D1") (pin "2") (pinfunction "2_2") (pintype "passive"))
      (node (ref "F1") (pin "2") (pinfunction "2_2") (pintype "passive"))
      (node (ref "R26") (pin "2") (pinfunction "2_2") (pintype "passive"))
      (node (ref "R27") (pin "2") (pinfunction "2_2") (pintype "passive"))
      (node (ref "R28") (pin "2") (pinfunction "2_2") (pintype "passive"))
      (node (ref "U1") (pin "3") (pinfunction "VIN_3") (pintype "passive"))
      (node (ref "U3") (pin "7") (pinfunction "VCC_7") (pintype "passive"))
    )
    (net (code "58") (name "VDD_3.3V") (class "Default")
      (node (ref "C2") (pin "1") (pinfunction "1_1") (pintype "passive"))
      (node (ref "C3") (pin "1") (pinfunction "1_1") (pintype "passive"))
      (node (ref "C4") (pin "1") (pinfunction "1_1") (pintype "passive"))
      (node (ref "C5") (pin "1") (pinfunction "1_1") (pintype "passive"))
      (node (ref "C6") (pin "2") (pinfunction "2_2") (pintype "passive"))
      (node (ref "C7") (pin "1") (pinfunction "1_1") (pintype "passive"))
      (node (ref "D6") (pin "1") (pinfunction "1_1") (pintype "passive"))
      (node (ref "JP1") (pin "1") (pinfunction "1_1") (pintype "passive"))
      (node (ref "JP2") (pin "1") (pinfunction "1_1") (pintype "passive"))
      (node (ref "JP3") (pin "1") (pinfunction "1_1") (pintype "passive"))
      (node (ref "JP5") (pin "1") (pinfunction "1_1") (pintype "passive"))
      (node (ref "LED1") (pin "1") (pinfunction "1_1") (pintype "passive"))
      (node (ref "LED2") (pin "1") (pinfunction "1_1") (pintype "passive"))
      (node (ref "LED3") (pin "1") (pinfunction "1_1") (pintype "passive"))
      (node (ref "Q1") (pin "2") (pinfunction "2_2") (pintype "passive"))
      (node (ref "R18") (pin "2") (pinfunction "2_2") (pintype "passive"))
      (node (ref "TP7") (pin "1") (pinfunction "1_1") (pintype "passive"))
      (node (ref "U1") (pin "2") (pinfunction "VOUT_2") (pintype "passive"))
      (node (ref "U2") (pin "1") (pinfunction "AVDD_MC_ADC_1") (pintype "passive"))
      (node (ref "U2") (pin "17") (pinfunction "VCCA_17") (pintype "passive"))
      (node (ref "U2") (pin "2") (pinfunction "AVDD_DAC/VDD33_2") (pintype "passive"))
      (node (ref "U2") (pin "7") (pinfunction "VDD33/AVDD_PLL_7") (pintype "passive"))
    )
    (net (code "59") (name "VIN") (class "Default")
      (node (ref "C12") (pin "1") (pinfunction "1_1") (pintype "passive"))
      (node (ref "JP4") (pin "1") (pinfunction "1_1") (pintype "passive"))
      (node (ref "Q1") (pin "3") (pinfunction "3_3") (pintype "passive"))
      (node (ref "R20") (pin "2") (pinfunction "2_2") (pintype "passive"))
    )
    (net (code "60") (name "unconnected-(P1-CC1-Pad4)") (class "Default")
      (node (ref "P1") (pin "4") (pinfunction "CC1_4") (pintype "passive"))
    )
    (net (code "61") (name "unconnected-(P1-CC2-Pad10)") (class "Default")
      (node (ref "P1") (pin "10") (pinfunction "CC2_10") (pintype "passive"))
    )
    (net (code "62") (name "unconnected-(P1-SBU1-Pad9)") (class "Default")
      (node (ref "P1") (pin "9") (pinfunction "SBU1_9") (pintype "passive"))
    )
    (net (code "63") (name "unconnected-(P1-SBU2-Pad3)") (class "Default")
      (node (ref "P1") (pin "3") (pinfunction "SBU2_3") (pintype "passive"))
    )
    (net (code "64") (name "unconnected-(U2-GINT[13]-Pad25)") (class "Default")
      (node (ref "U2") (pin "25") (pinfunction "GINT[13]_25") (pintype "passive"))
    )
    (net (code "65") (name "unconnected-(U2-ISOCLK2-Pad4)") (class "Default")
      (node (ref "U2") (pin "4") (pinfunction "ISOCLK2_4") (pintype "passive"))
    )
    (net (code "66") (name "unconnected-(U2-ISODAT2-Pad3)") (class "Default")
      (node (ref "U2") (pin "3") (pinfunction "ISODAT2_3") (pintype "passive"))
    )
    (net (code "67") (name "unconnected-(U2-ISORST2-Pad5)") (class "Default")
      (node (ref "U2") (pin "5") (pinfunction "ISORST2_5") (pintype "passive"))
    )
    (net (code "68") (name "unconnected-(U2-MOSI1-Pad27)") (class "Default")
      (node (ref "U2") (pin "27") (pinfunction "MOSI1_27") (pintype "passive"))
    )
    (net (code "69") (name "unconnected-(U2-SCK1-Pad26)") (class "Default")
      (node (ref "U2") (pin "26") (pinfunction "SCK1_26") (pintype "passive"))
    )
    (net (code "70") (name "unconnected-(U2-VDDIO_CARD0-Pad6)") (class "Default")
      (node (ref "U2") (pin "6") (pinfunction "VDDIO_CARD0_6") (pintype "passive"))
    )
    (net (code "71") (name "unconnected-(U3-CTS#-Pad5)") (class "Default")
      (node (ref "U3") (pin "5") (pinfunction "CTS#_5") (pintype "passive"))
    )
    (net (code "72") (name "unconnected-(U3-RTS#-Pad4)") (class "Default")
      (node (ref "U3") (pin "4") (pinfunction "RTS#_4") (pintype "passive"))
    )
    (net (code "73") (name "unconnected-(U3-TNOW-Pad6)") (class "Default")
      (node (ref "U3") (pin "6") (pinfunction "TNOW_6") (pintype "passive"))
    )
  )
)
